# Schematic.net
KiCad netlist of a schematic drawn in EAGLE
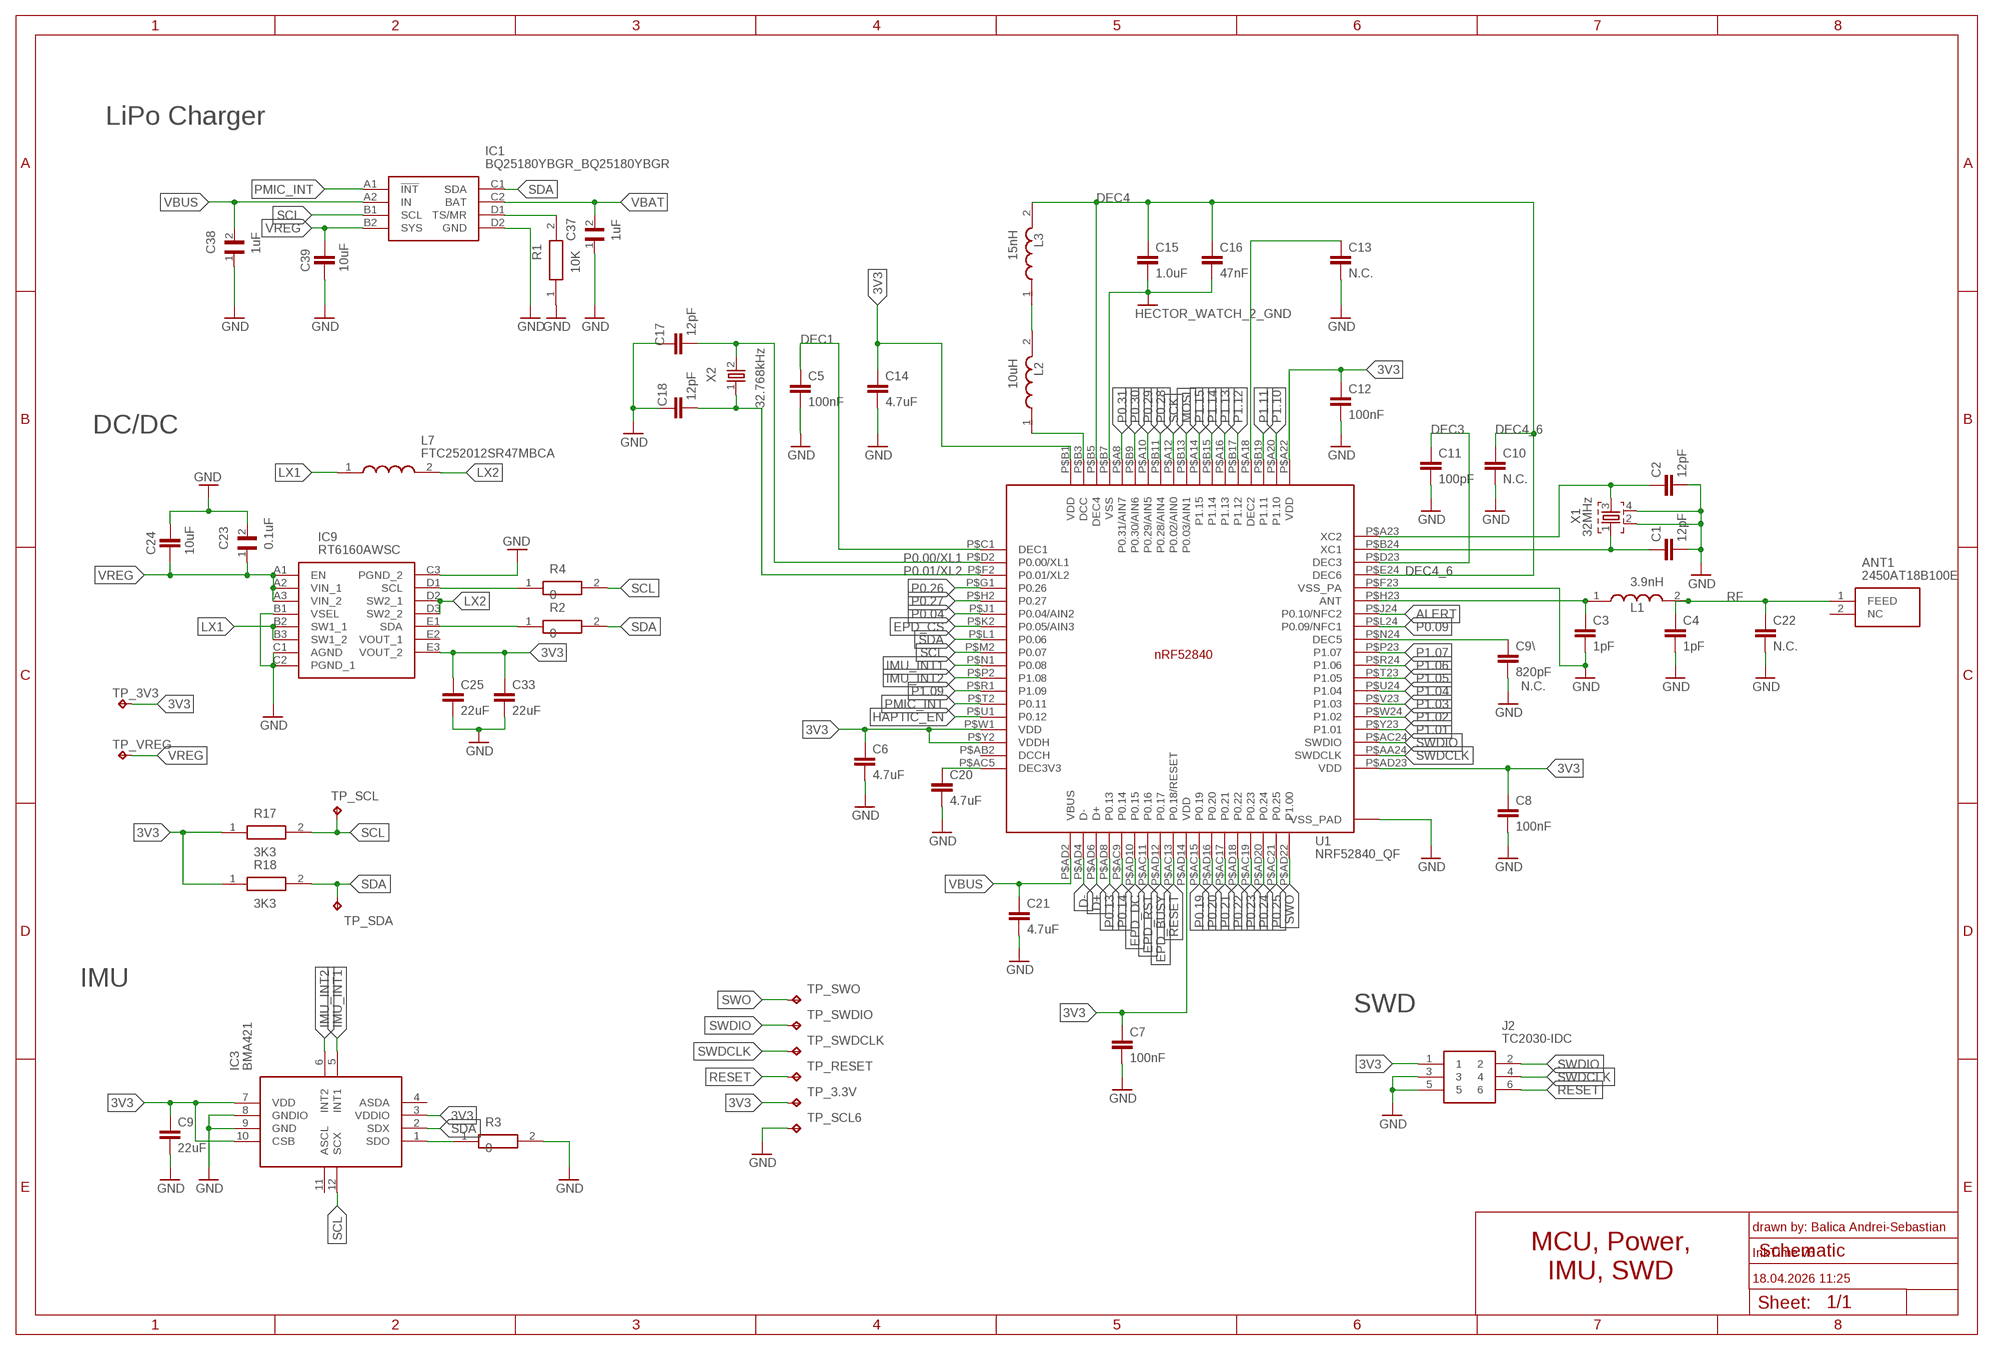
[diagram p0: schematic, sheet 1, part 1 of 2]
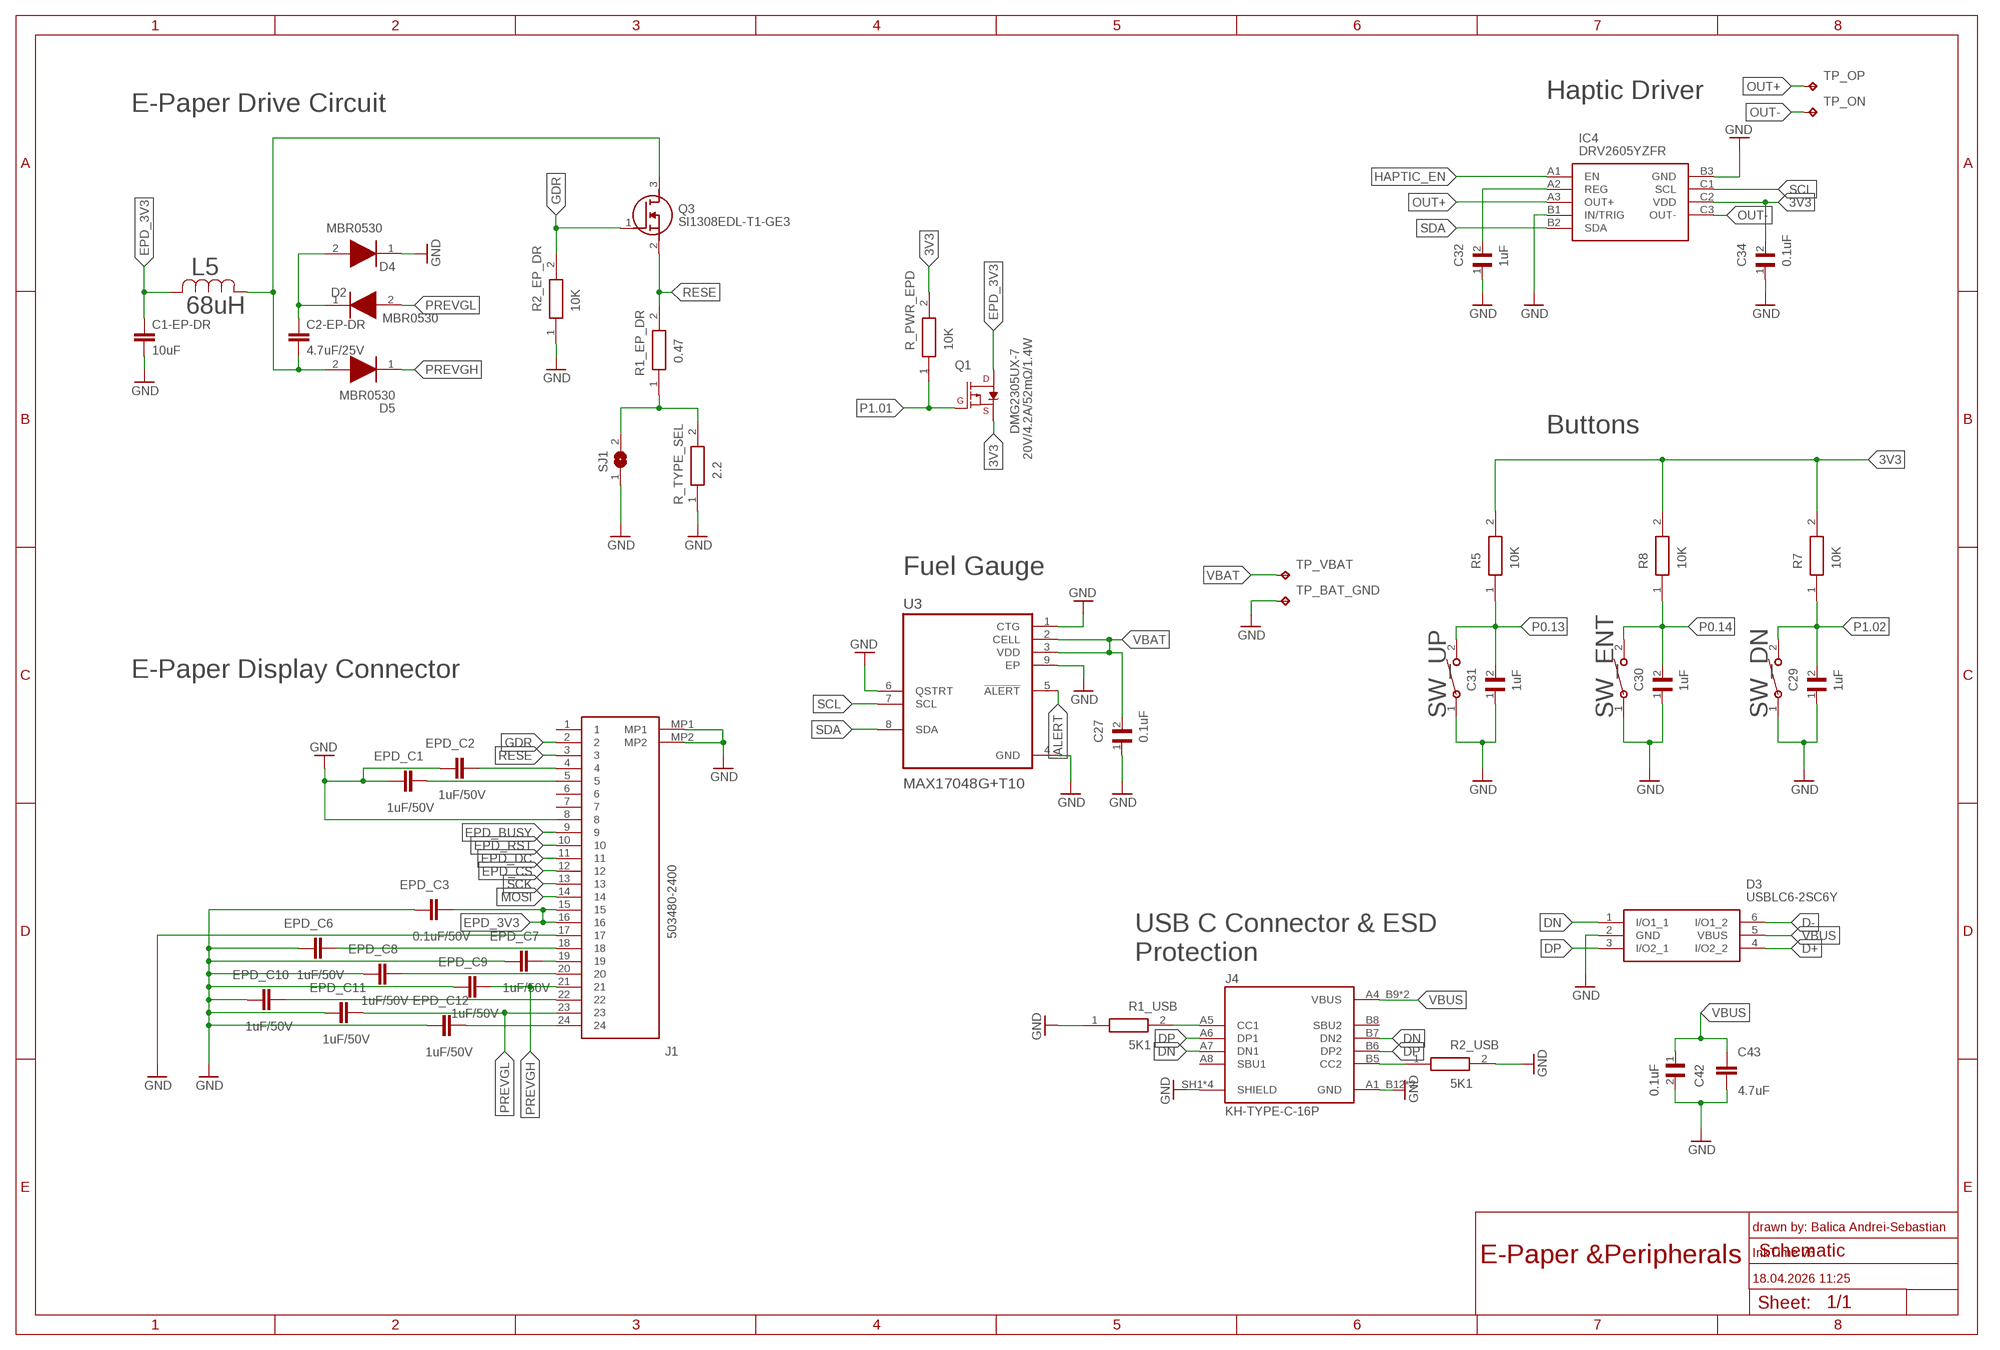
[diagram p1: schematic, sheet 1, part 2 of 2]

(export (version "E")
  (design (tool "Eeschema 10.0.6"))
  (components
    (comp (ref "ANT1")
      (value "2450AT18B100E")
      (footprint "eagle-import:2450AT18B100E_ANTC3216X140N")
      (fields (field (name "MOUSER_PART_NUMBER") "609-2450AT18B100E"))
      (libsource (lib "eagle-import") (part "2450AT18B100E_2450AT18B100E"))
    )
    (comp (ref "C1")
      (value "12pF")
      (footprint "eagle-import:NORDIC_NRF_3_RESC0201_L")
      (libsource (lib "eagle-import") (part "NORDIC_NRF_3_CAPACITOR_0201_L"))
    )
    (comp (ref "C1-EP-DR")
      (value "10uF")
      (footprint "eagle-import:NORDIC_NRF_3_RESC0201_L")
      (libsource (lib "eagle-import") (part "NORDIC_NRF_3_CAPACITOR_0201_L"))
    )
    (comp (ref "C2")
      (value "12pF")
      (footprint "eagle-import:NORDIC_NRF_3_RESC0201_L")
      (libsource (lib "eagle-import") (part "NORDIC_NRF_3_CAPACITOR_0201_L"))
    )
    (comp (ref "C2-EP-DR")
      (value "4.7uF/25V")
      (footprint "eagle-import:NORDIC_NRF_3_RESC0201_L")
      (libsource (lib "eagle-import") (part "NORDIC_NRF_3_CAPACITOR_0201_L"))
    )
    (comp (ref "C3")
      (value "1pF")
      (footprint "eagle-import:NORDIC_NRF_3_RESC0201_L")
      (libsource (lib "eagle-import") (part "NORDIC_NRF_3_CAPACITOR_0201_L"))
    )
    (comp (ref "C4")
      (value "1pF")
      (footprint "eagle-import:NORDIC_NRF_3_RESC0201_L")
      (libsource (lib "eagle-import") (part "NORDIC_NRF_3_CAPACITOR_0201_L"))
    )
    (comp (ref "C5")
      (value "100nF")
      (footprint "eagle-import:NORDIC_NRF_3_RESC0201_L")
      (libsource (lib "eagle-import") (part "NORDIC_NRF_3_CAPACITOR_0201_L"))
    )
    (comp (ref "C6")
      (value "4.7uF")
      (footprint "eagle-import:NORDIC_NRF_3_RESC0201_L")
      (libsource (lib "eagle-import") (part "NORDIC_NRF_3_CAPACITOR_0201_L"))
    )
    (comp (ref "C7")
      (value "100nF")
      (footprint "eagle-import:NORDIC_NRF_3_RESC0201_L")
      (libsource (lib "eagle-import") (part "NORDIC_NRF_3_CAPACITOR_0201_L"))
    )
    (comp (ref "C8")
      (value "100nF")
      (footprint "eagle-import:NORDIC_NRF_3_RESC0201_L")
      (libsource (lib "eagle-import") (part "NORDIC_NRF_3_CAPACITOR_0201_L"))
    )
    (comp (ref "C9")
      (value "22uF")
      (footprint "eagle-import:NORDIC_NRF_3_RESC0201_L")
      (libsource (lib "eagle-import") (part "NORDIC_NRF_3_CAPACITOR_0201_L"))
    )
    (comp (ref "C9\\")
      (value "820pF")
      (footprint "eagle-import:NORDIC_NRF_3_RESC0201_L")
      (libsource (lib "eagle-import") (part "NORDIC_NRF_3_CAPACITOR_0201_L"))
    )
    (comp (ref "C10")
      (value "N.C.")
      (footprint "eagle-import:NORDIC_NRF_3_RESC0201_L")
      (libsource (lib "eagle-import") (part "NORDIC_NRF_3_CAPACITOR_0201_L"))
    )
    (comp (ref "C11")
      (value "100pF")
      (footprint "eagle-import:NORDIC_NRF_3_RESC0201_L")
      (libsource (lib "eagle-import") (part "NORDIC_NRF_3_CAPACITOR_0201_L"))
    )
    (comp (ref "C12")
      (value "100nF")
      (footprint "eagle-import:NORDIC_NRF_3_RESC0201_L")
      (libsource (lib "eagle-import") (part "NORDIC_NRF_3_CAPACITOR_0201_L"))
    )
    (comp (ref "C13")
      (value "N.C.")
      (footprint "eagle-import:NORDIC_NRF_3_RESC0201_L")
      (libsource (lib "eagle-import") (part "NORDIC_NRF_3_CAPACITOR_0201_L"))
    )
    (comp (ref "C14")
      (value "4.7uF")
      (footprint "eagle-import:NORDIC_NRF_3_RESC0201_L")
      (libsource (lib "eagle-import") (part "NORDIC_NRF_3_CAPACITOR_0201_L"))
    )
    (comp (ref "C15")
      (value "1.0uF")
      (footprint "eagle-import:NORDIC_NRF_3_RESC0201_L")
      (libsource (lib "eagle-import") (part "NORDIC_NRF_3_CAPACITOR_0201_L"))
    )
    (comp (ref "C16")
      (value "47nF")
      (footprint "eagle-import:NORDIC_NRF_3_RESC0201_L")
      (libsource (lib "eagle-import") (part "NORDIC_NRF_3_CAPACITOR_0201_L"))
    )
    (comp (ref "C17")
      (value "12pF")
      (footprint "eagle-import:NORDIC_NRF_3_RESC0201_L")
      (libsource (lib "eagle-import") (part "NORDIC_NRF_3_CAPACITOR_0201_L"))
    )
    (comp (ref "C18")
      (value "12pF")
      (footprint "eagle-import:NORDIC_NRF_3_RESC0201_L")
      (libsource (lib "eagle-import") (part "NORDIC_NRF_3_CAPACITOR_0201_L"))
    )
    (comp (ref "C20")
      (value "4.7uF")
      (footprint "eagle-import:NORDIC_NRF_3_RESC0201_L")
      (libsource (lib "eagle-import") (part "NORDIC_NRF_3_CAPACITOR_0201_L"))
    )
    (comp (ref "C21")
      (value "4.7uF")
      (footprint "eagle-import:NORDIC_NRF_3_RESC0201_L")
      (libsource (lib "eagle-import") (part "NORDIC_NRF_3_CAPACITOR_0201_L"))
    )
    (comp (ref "C22")
      (value "N.C.")
      (footprint "eagle-import:NORDIC_NRF_3_RESC0201_L")
      (libsource (lib "eagle-import") (part "NORDIC_NRF_3_CAPACITOR_0201_L"))
    )
    (comp (ref "C23")
      (value "0.1uF")
      (footprint "eagle-import:GRM011R60J152KE01L_2_CAPC0201X13N")
      (fields (field (name "MF") "Murata") (field (name "MP") "GRM011R60J152KE01L"))
      (libsource (lib "eagle-import") (part "GRM011R60J152KE01L_2_GRM011R60J152KE01L"))
    )
    (comp (ref "C24")
      (value "10uF")
      (footprint "eagle-import:NORDIC_NRF_3_RESC0201_L")
      (libsource (lib "eagle-import") (part "NORDIC_NRF_3_CAPACITOR_0201_L"))
    )
    (comp (ref "C25")
      (value "22uF")
      (footprint "eagle-import:NORDIC_NRF_3_RESC0201_L")
      (libsource (lib "eagle-import") (part "NORDIC_NRF_3_CAPACITOR_0201_L"))
    )
    (comp (ref "C27")
      (value "0.1uF")
      (footprint "eagle-import:GRM011R60J152KE01L_2_CAPC0201X13N")
      (fields (field (name "MF") "Murata") (field (name "MP") "GRM011R60J152KE01L"))
      (libsource (lib "eagle-import") (part "GRM011R60J152KE01L_2_GRM011R60J152KE01L"))
    )
    (comp (ref "C29")
      (value "1uF")
      (footprint "eagle-import:GRM011R60J152KE01L_2_CAPC0201X13N")
      (fields (field (name "MF") "Murata") (field (name "MP") "GRM011R60J152KE01L"))
      (libsource (lib "eagle-import") (part "GRM011R60J152KE01L_2_GRM011R60J152KE01L"))
    )
    (comp (ref "C30")
      (value "1uF")
      (footprint "eagle-import:GRM011R60J152KE01L_2_CAPC0201X13N")
      (fields (field (name "MF") "Murata") (field (name "MP") "GRM011R60J152KE01L"))
      (libsource (lib "eagle-import") (part "GRM011R60J152KE01L_2_GRM011R60J152KE01L"))
    )
    (comp (ref "C31")
      (value "1uF")
      (footprint "eagle-import:GRM011R60J152KE01L_2_CAPC0201X13N")
      (fields (field (name "MF") "Murata") (field (name "MP") "GRM011R60J152KE01L"))
      (libsource (lib "eagle-import") (part "GRM011R60J152KE01L_2_GRM011R60J152KE01L"))
    )
    (comp (ref "C32")
      (value "1uF")
      (footprint "eagle-import:GRM011R60J152KE01L_2_CAPC0201X13N")
      (fields (field (name "MF") "Murata") (field (name "MP") "GRM011R60J152KE01L"))
      (libsource (lib "eagle-import") (part "GRM011R60J152KE01L_2_GRM011R60J152KE01L"))
    )
    (comp (ref "C33")
      (value "22uF")
      (footprint "eagle-import:NORDIC_NRF_3_RESC0201_L")
      (libsource (lib "eagle-import") (part "NORDIC_NRF_3_CAPACITOR_0201_L"))
    )
    (comp (ref "C34")
      (value "0.1uF")
      (footprint "eagle-import:GRM011R60J152KE01L_2_CAPC0201X13N")
      (fields (field (name "MF") "Murata") (field (name "MP") "GRM011R60J152KE01L"))
      (libsource (lib "eagle-import") (part "GRM011R60J152KE01L_2_GRM011R60J152KE01L"))
    )
    (comp (ref "C37")
      (value "1uF")
      (footprint "eagle-import:GRM011R60J152KE01L_2_CAPC0201X13N")
      (fields (field (name "MF") "Murata") (field (name "MP") "GRM011R60J152KE01L"))
      (libsource (lib "eagle-import") (part "GRM011R60J152KE01L_2_GRM011R60J152KE01L"))
    )
    (comp (ref "C38")
      (value "1uF")
      (footprint "eagle-import:GRM011R60J152KE01L_2_CAPC0201X13N")
      (fields (field (name "MF") "Murata") (field (name "MP") "GRM011R60J152KE01L"))
      (libsource (lib "eagle-import") (part "GRM011R60J152KE01L_2_GRM011R60J152KE01L"))
    )
    (comp (ref "C39")
      (value "10uF")
      (footprint "eagle-import:NORDIC_NRF_3_RESC0201_L")
      (libsource (lib "eagle-import") (part "NORDIC_NRF_3_CAPACITOR_0201_L"))
    )
    (comp (ref "C42")
      (value "0.1uF")
      (footprint "eagle-import:GRM011R60J152KE01L_2_CAPC0201X13N")
      (fields (field (name "MF") "Murata") (field (name "MP") "GRM011R60J152KE01L"))
      (libsource (lib "eagle-import") (part "GRM011R60J152KE01L_2_GRM011R60J152KE01L"))
    )
    (comp (ref "C43")
      (value "4.7uF")
      (footprint "eagle-import:NORDIC_NRF_3_RESC0201_L")
      (libsource (lib "eagle-import") (part "NORDIC_NRF_3_CAPACITOR_0201_L"))
    )
    (comp (ref "D2")
      (value "MBR0530")
      (footprint "eagle-import:ESP32_C6_LIBRARY_5_SOD3716X135N")
      (fields (field (name "MF") "ON Semiconductor"))
      (libsource (lib "eagle-import") (part "ESP32_C6_LIBRARY_5_MBR0530"))
    )
    (comp (ref "D3")
      (value "USBLC6-2SC6Y")
      (footprint "eagle-import:ESP32_C6_LIBRARY_3_SOT95P280X145-6N")
      (fields (field (name "MF") "STMicroelectronics"))
      (libsource (lib "eagle-import") (part "ESP32_C6_LIBRARY_3_USBLC6-2SC6Y"))
    )
    (comp (ref "D4")
      (value "MBR0530")
      (footprint "eagle-import:ESP32_C6_LIBRARY_5_SOD3716X135N")
      (fields (field (name "MF") "ON Semiconductor"))
      (libsource (lib "eagle-import") (part "ESP32_C6_LIBRARY_5_MBR0530"))
    )
    (comp (ref "D5")
      (value "MBR0530")
      (footprint "eagle-import:ESP32_C6_LIBRARY_5_SOD3716X135N")
      (fields (field (name "MF") "ON Semiconductor"))
      (libsource (lib "eagle-import") (part "ESP32_C6_LIBRARY_5_MBR0530"))
    )
    (comp (ref "EPD_C1")
      (value "1uF/50V")
      (footprint "eagle-import:NORDIC_NRF_3_RESC0201_L")
      (libsource (lib "eagle-import") (part "NORDIC_NRF_3_CAPACITOR_0201_L"))
    )
    (comp (ref "EPD_C2")
      (value "1uF/50V")
      (footprint "eagle-import:NORDIC_NRF_3_RESC0201_L")
      (libsource (lib "eagle-import") (part "NORDIC_NRF_3_CAPACITOR_0201_L"))
    )
    (comp (ref "EPD_C3")
      (value "0.1uF/50V")
      (footprint "eagle-import:NORDIC_NRF_3_RESC0201_L")
      (libsource (lib "eagle-import") (part "NORDIC_NRF_3_CAPACITOR_0201_L"))
    )
    (comp (ref "EPD_C6")
      (value "1uF/50V")
      (footprint "eagle-import:NORDIC_NRF_3_RESC0201_L")
      (libsource (lib "eagle-import") (part "NORDIC_NRF_3_CAPACITOR_0201_L"))
    )
    (comp (ref "EPD_C7")
      (value "1uF/50V")
      (footprint "eagle-import:NORDIC_NRF_3_RESC0201_L")
      (libsource (lib "eagle-import") (part "NORDIC_NRF_3_CAPACITOR_0201_L"))
    )
    (comp (ref "EPD_C8")
      (value "1uF/50V")
      (footprint "eagle-import:NORDIC_NRF_3_RESC0201_L")
      (libsource (lib "eagle-import") (part "NORDIC_NRF_3_CAPACITOR_0201_L"))
    )
    (comp (ref "EPD_C9")
      (value "1uF/50V")
      (footprint "eagle-import:NORDIC_NRF_3_RESC0201_L")
      (libsource (lib "eagle-import") (part "NORDIC_NRF_3_CAPACITOR_0201_L"))
    )
    (comp (ref "EPD_C10")
      (value "1uF/50V")
      (footprint "eagle-import:NORDIC_NRF_3_RESC0201_L")
      (libsource (lib "eagle-import") (part "NORDIC_NRF_3_CAPACITOR_0201_L"))
    )
    (comp (ref "EPD_C11")
      (value "1uF/50V")
      (footprint "eagle-import:NORDIC_NRF_3_RESC0201_L")
      (libsource (lib "eagle-import") (part "NORDIC_NRF_3_CAPACITOR_0201_L"))
    )
    (comp (ref "EPD_C12")
      (value "1uF/50V")
      (footprint "eagle-import:NORDIC_NRF_3_RESC0201_L")
      (libsource (lib "eagle-import") (part "NORDIC_NRF_3_CAPACITOR_0201_L"))
    )
    (comp (ref "IC1")
      (value "BQ25180YBGR_BQ25180YBGR")
      (footprint "eagle-import:BQ25180YBGR_BGA8C40P2X4_100X155X50")
      (fields
        (field (name "ARROW_PART_NUMBER") "BQ25180YBGR")
        (field (name "MOUSER_PART_NUMBER") "595-BQ25180YBGR")
      )
      (libsource (lib "eagle-import") (part "BQ25180YBGR_BQ25180YBGR"))
    )
    (comp (ref "IC3")
      (value "BMA421")
      (footprint "eagle-import:BMA423_BMA423")
      (fields (field (name "ARROW_PART_NUMBER") "BMA423") (field (name "MOUSER_PART_NUMBER") "262-BMA423"))
      (libsource (lib "eagle-import") (part "BMA423_BMA423"))
    )
    (comp (ref "IC4")
      (value "DRV2605YZFR")
      (footprint "eagle-import:DRV2605YZFR_BGA9C50P3X3_144X144X62")
      (libsource (lib "eagle-import") (part "DRV2605YZFR_DRV2605YZFR"))
    )
    (comp (ref "IC9")
      (value "RT6160AWSC")
      (footprint "eagle-import:RT6160AWSC_BGA15C40P3X5_140X230X60")
      (fields (field (name "MOUSER_PART_NUMBER") "835-RT6160AWSC"))
      (libsource (lib "eagle-import") (part "RT6160AWSC_RT6160AWSC"))
    )
    (comp (ref "J1")
      (value "503480-2400")
      (footprint "eagle-import:503480-2400_5034802400")
      (fields (field (name "MOUSER_PART_NUMBER") "538-503480-2400"))
      (libsource (lib "eagle-import") (part "503480-2400_503480-2400"))
    )
    (comp (ref "J2")
      (value "TC2030-IDC")
      (footprint "eagle-import:TC2030-IDC_TC2030IDC")
      (libsource (lib "eagle-import") (part "TC2030-IDC_TC2030-IDC"))
    )
    (comp (ref "J4")
      (value "KH-TYPE-C-16P")
      (footprint "eagle-import:KH-TYPE-C-16P_KINGHELM_KH-TYPE-C-16P")
      (fields (field (name "MF") "kinghelm"))
      (libsource (lib "eagle-import") (part "KH-TYPE-C-16P_KH-TYPE-C-16P"))
    )
    (comp (ref "L1")
      (value "3.9nH")
      (footprint "eagle-import:MLP2016SR47MT0S1_INDC2016X100N")
      (fields (field (name "MANUFACTURER_PART_NUMBER") "FTC252012SR47MBCA"))
      (libsource (lib "eagle-import") (part "MLP2016SR47MT0S1_FTC252012SR47MBCA"))
    )
    (comp (ref "L2")
      (value "10uH")
      (footprint "eagle-import:MLP2016SR47MT0S1_INDC2016X100N")
      (fields (field (name "MANUFACTURER_PART_NUMBER") "FTC252012SR47MBCA"))
      (libsource (lib "eagle-import") (part "MLP2016SR47MT0S1_FTC252012SR47MBCA"))
    )
    (comp (ref "L3")
      (value "15nH")
      (footprint "eagle-import:MLP2016SR47MT0S1_INDC2016X100N")
      (fields (field (name "MANUFACTURER_PART_NUMBER") "FTC252012SR47MBCA"))
      (libsource (lib "eagle-import") (part "MLP2016SR47MT0S1_FTC252012SR47MBCA"))
    )
    (comp (ref "L5")
      (value "68uH")
      (footprint "eagle-import:ESP32_C6_LIBRARY_2_IND_4828-WE-TPC_WRE")
      (fields
        (field (name "MANUFACTURER_PART_NUMBER") "744043680")
        (field (name "COPYRIGHT") "Copyright (C) 2024 Ultra Librarian. All rights reserved.")
      )
      (libsource (lib "eagle-import") (part "ESP32_C6_LIBRARY_2_744043680IND_4828-WE-TPC_WRE"))
    )
    (comp (ref "L7")
      (value "FTC252012SR47MBCA")
      (footprint "eagle-import:MLP2016SR47MT0S1_INDC2016X100N")
      (libsource (lib "eagle-import") (part "MLP2016SR47MT0S1_FTC252012SR47MBCA"))
    )
    (comp (ref "Q1")
      (value "20V/4.2A/52mΩ/1.4W")
      (footprint "eagle-import:ESP32_C6_LIBRARY_4_ESP32_C6_LIBRARY_4_ESP32_C6_LIBRARY_4_ESP32_C6_LIBRARY_4_ESP32_WROVER_SPARKFUN-DISCRETESEMI_SOT23-3")
      (libsource (lib "eagle-import") (part "ESP32_C6_LIBRARY_4_ESP32_WROVER_SPARKFUN-DISCRETESEMI_MOSFET_PCH-DMG2305UX-7"))
    )
    (comp (ref "Q3")
      (value "SI1308EDL-T1-GE3")
      (footprint "eagle-import:ESP32_C6_LIBRARY_6_SOT65P210X110-3N")
      (fields (field (name "MF") "Vishay Siliconix"))
      (libsource (lib "eagle-import") (part "ESP32_C6_LIBRARY_6_SI1308EDL-T1-GE3"))
    )
    (comp (ref "R1")
      (value "10K")
      (footprint "eagle-import:ERA-1AEB3401C_0201")
      (libsource (lib "eagle-import") (part "ERA-1AEB3401C_CPF0201D7K68C1"))
    )
    (comp (ref "R1_EP_DR")
      (value "0.47")
      (footprint "eagle-import:ERA-1AEB3401C_0201")
      (libsource (lib "eagle-import") (part "ERA-1AEB3401C_CPF0201D7K68C1"))
    )
    (comp (ref "R1_USB")
      (value "5K1")
      (footprint "eagle-import:ERA-1AEB3401C_0201")
      (libsource (lib "eagle-import") (part "ERA-1AEB3401C_CPF0201D7K68C1"))
    )
    (comp (ref "R2")
      (value "0")
      (footprint "eagle-import:ERA-1AEB3401C_0201")
      (libsource (lib "eagle-import") (part "ERA-1AEB3401C_CPF0201D7K68C1"))
    )
    (comp (ref "R2_EP_DR")
      (value "10K")
      (footprint "eagle-import:ERA-1AEB3401C_0201")
      (libsource (lib "eagle-import") (part "ERA-1AEB3401C_CPF0201D7K68C1"))
    )
    (comp (ref "R2_USB")
      (value "5K1")
      (footprint "eagle-import:ERA-1AEB3401C_0201")
      (libsource (lib "eagle-import") (part "ERA-1AEB3401C_CPF0201D7K68C1"))
    )
    (comp (ref "R3")
      (value "0")
      (footprint "eagle-import:ERA-1AEB3401C_0201")
      (libsource (lib "eagle-import") (part "ERA-1AEB3401C_CPF0201D7K68C1"))
    )
    (comp (ref "R4")
      (value "0")
      (footprint "eagle-import:ERA-1AEB3401C_0201")
      (libsource (lib "eagle-import") (part "ERA-1AEB3401C_CPF0201D7K68C1"))
    )
    (comp (ref "R5")
      (value "10K")
      (footprint "eagle-import:ERA-1AEB3401C_0201")
      (libsource (lib "eagle-import") (part "ERA-1AEB3401C_CPF0201D7K68C1"))
    )
    (comp (ref "R7")
      (value "10K")
      (footprint "eagle-import:ERA-1AEB3401C_0201")
      (libsource (lib "eagle-import") (part "ERA-1AEB3401C_CPF0201D7K68C1"))
    )
    (comp (ref "R8")
      (value "10K")
      (footprint "eagle-import:ERA-1AEB3401C_0201")
      (libsource (lib "eagle-import") (part "ERA-1AEB3401C_CPF0201D7K68C1"))
    )
    (comp (ref "R17")
      (value "3K3")
      (footprint "eagle-import:ERA-1AEB3401C_0201")
      (libsource (lib "eagle-import") (part "ERA-1AEB3401C_CPF0201D7K68C1"))
    )
    (comp (ref "R18")
      (value "3K3")
      (footprint "eagle-import:ERA-1AEB3401C_0201")
      (libsource (lib "eagle-import") (part "ERA-1AEB3401C_CPF0201D7K68C1"))
    )
    (comp (ref "R_PWR_EPD")
      (value "10K")
      (footprint "eagle-import:ERA-1AEB3401C_0201")
      (libsource (lib "eagle-import") (part "ERA-1AEB3401C_CPF0201D7K68C1"))
    )
    (comp (ref "R_TYPE_SEL")
      (value "2.2")
      (footprint "eagle-import:ERA-1AEB3401C_0201")
      (libsource (lib "eagle-import") (part "ERA-1AEB3401C_CPF0201D7K68C1"))
    )
    (comp (ref "SJ1")
      (value "ESP32_C6_LIBRARY_7_JUMPER_SJ")
      (footprint "eagle-import:ESP32_C6_LIBRARY_7_JUMPER_SJ")
      (libsource (lib "eagle-import") (part "ESP32_C6_LIBRARY_7_JUMPER_SJ"))
    )
    (comp (ref "SW_DN")
      (value "2025-10-22_07-23-44_LIBRARY_EVP-AKE31ASW_EVP-AKE31A_PAN")
      (footprint "eagle-import:2025-10-22_07-23-44_LIBRARY_SW_EVP-AKE31A_PAN")
      (fields
        (field (name "MANUFACTURER_PART_NUMBER") "EVP-AKE31A")
        (field (name "COPYRIGHT") "Copyright (C) 2025 Ultra Librarian. All rights reserved.")
      )
      (libsource (lib "eagle-import") (part "2025-10-22_07-23-44_LIBRARY_EVP-AKE31ASW_EVP-AKE31A_PAN"))
    )
    (comp (ref "SW_ENT")
      (value "2025-10-22_07-23-44_LIBRARY_EVP-AKE31ASW_EVP-AKE31A_PAN")
      (footprint "eagle-import:2025-10-22_07-23-44_LIBRARY_SW_EVP-AKE31A_PAN")
      (fields
        (field (name "MANUFACTURER_PART_NUMBER") "EVP-AKE31A")
        (field (name "COPYRIGHT") "Copyright (C) 2025 Ultra Librarian. All rights reserved.")
      )
      (libsource (lib "eagle-import") (part "2025-10-22_07-23-44_LIBRARY_EVP-AKE31ASW_EVP-AKE31A_PAN"))
    )
    (comp (ref "SW_UP")
      (value "2025-10-22_07-23-44_LIBRARY_EVP-AKE31ASW_EVP-AKE31A_PAN")
      (footprint "eagle-import:2025-10-22_07-23-44_LIBRARY_SW_EVP-AKE31A_PAN")
      (fields
        (field (name "MANUFACTURER_PART_NUMBER") "EVP-AKE31A")
        (field (name "COPYRIGHT") "Copyright (C) 2025 Ultra Librarian. All rights reserved.")
      )
      (libsource (lib "eagle-import") (part "2025-10-22_07-23-44_LIBRARY_EVP-AKE31ASW_EVP-AKE31A_PAN"))
    )
    (comp (ref "TP_3.3V")
      (value "HECTOR_WATCH_1_TPTP20R")
      (footprint "eagle-import:HECTOR_WATCH_1_TP20R")
      (libsource (lib "eagle-import") (part "HECTOR_WATCH_1_TPTP20R"))
    )
    (comp (ref "TP_3V3")
      (value "HECTOR_WATCH_1_TPTP20R")
      (footprint "eagle-import:HECTOR_WATCH_1_TP20R")
      (libsource (lib "eagle-import") (part "HECTOR_WATCH_1_TPTP20R"))
    )
    (comp (ref "TP_BAT_GND")
      (value "HECTOR_WATCH_1_TPTP20R")
      (footprint "eagle-import:HECTOR_WATCH_1_TP20R")
      (libsource (lib "eagle-import") (part "HECTOR_WATCH_1_TPTP20R"))
    )
    (comp (ref "TP_ON")
      (value "HECTOR_WATCH_1_TPTP20R")
      (footprint "eagle-import:HECTOR_WATCH_1_TP20R")
      (libsource (lib "eagle-import") (part "HECTOR_WATCH_1_TPTP20R"))
    )
    (comp (ref "TP_OP")
      (value "HECTOR_WATCH_1_TPTP20R")
      (footprint "eagle-import:HECTOR_WATCH_1_TP20R")
      (libsource (lib "eagle-import") (part "HECTOR_WATCH_1_TPTP20R"))
    )
    (comp (ref "TP_RESET")
      (value "HECTOR_WATCH_1_TPTP20R")
      (footprint "eagle-import:HECTOR_WATCH_1_TP20R")
      (libsource (lib "eagle-import") (part "HECTOR_WATCH_1_TPTP20R"))
    )
    (comp (ref "TP_SCL")
      (value "HECTOR_WATCH_1_TPTP20R")
      (footprint "eagle-import:HECTOR_WATCH_1_TP20R")
      (libsource (lib "eagle-import") (part "HECTOR_WATCH_1_TPTP20R"))
    )
    (comp (ref "TP_SCL6")
      (value "HECTOR_WATCH_1_TPTP20R")
      (footprint "eagle-import:HECTOR_WATCH_1_TP20R")
      (libsource (lib "eagle-import") (part "HECTOR_WATCH_1_TPTP20R"))
    )
    (comp (ref "TP_SDA")
      (value "HECTOR_WATCH_1_TPTP20R")
      (footprint "eagle-import:HECTOR_WATCH_1_TP20R")
      (libsource (lib "eagle-import") (part "HECTOR_WATCH_1_TPTP20R"))
    )
    (comp (ref "TP_SWDCLK")
      (value "HECTOR_WATCH_1_TPTP20R")
      (footprint "eagle-import:HECTOR_WATCH_1_TP20R")
      (libsource (lib "eagle-import") (part "HECTOR_WATCH_1_TPTP20R"))
    )
    (comp (ref "TP_SWDIO")
      (value "HECTOR_WATCH_1_TPTP20R")
      (footprint "eagle-import:HECTOR_WATCH_1_TP20R")
      (libsource (lib "eagle-import") (part "HECTOR_WATCH_1_TPTP20R"))
    )
    (comp (ref "TP_SWO")
      (value "HECTOR_WATCH_1_TPTP20R")
      (footprint "eagle-import:HECTOR_WATCH_1_TP20R")
      (libsource (lib "eagle-import") (part "HECTOR_WATCH_1_TPTP20R"))
    )
    (comp (ref "TP_VBAT")
      (value "HECTOR_WATCH_1_TPTP20R")
      (footprint "eagle-import:HECTOR_WATCH_1_TP20R")
      (libsource (lib "eagle-import") (part "HECTOR_WATCH_1_TPTP20R"))
    )
    (comp (ref "TP_VREG")
      (value "HECTOR_WATCH_1_TPTP20R")
      (footprint "eagle-import:HECTOR_WATCH_1_TP20R")
      (libsource (lib "eagle-import") (part "HECTOR_WATCH_1_TPTP20R"))
    )
    (comp (ref "U1")
      (value "NRF52840_QF")
      (footprint "eagle-import:NORDIC_NRF_4_AQFN50P700X700X85_HS-74N")
      (libsource (lib "eagle-import") (part "NORDIC_NRF_4_NRF52840_QF"))
    )
    (comp (ref "U3")
      (value "MAX17048G+T10")
      (footprint "eagle-import:ESP32_C6_LIBRARY_SON50P200X200X80-9N")
      (fields (field (name "MF") "Analog Devices"))
      (libsource (lib "eagle-import") (part "ESP32_C6_LIBRARY_MAX17048G+T10"))
    )
    (comp (ref "X1")
      (value "32MHz")
      (footprint "eagle-import:NORDIC_NRF_BT-XTAL_2016_N")
      (libsource (lib "eagle-import") (part "NORDIC_NRF_XTAL_32MHZ"))
    )
    (comp (ref "X2")
      (value "32.768kHz")
      (footprint "eagle-import:NORDIC_NRF_1_XTAL_3215_N")
      (libsource (lib "eagle-import") (part "NORDIC_NRF_1_XTAL_32KHZ"))
    )
  )
  (nets
    (net (code "1") (name "/DEC3") (class "Default")
      (node (ref "C11") (pin "1") (pinfunction "1_1") (pintype "passive"))
      (node (ref "U1") (pin "P$D23") (pinfunction "DEC3_P$D23") (pintype "bidirectional"))
    )
    (net (code "2") (name "/DEC4_6") (class "Default")
      (node (ref "C10") (pin "1") (pinfunction "1_1") (pintype "passive"))
      (node (ref "C15") (pin "1") (pinfunction "1_1") (pintype "passive"))
      (node (ref "C16") (pin "1") (pinfunction "1_1") (pintype "passive"))
      (node (ref "L3") (pin "2") (pinfunction "2_2") (pintype "bidirectional"))
      (node (ref "U1") (pin "P$B5") (pinfunction "DEC4_P$B5") (pintype "power_in"))
      (node (ref "U1") (pin "P$E24") (pinfunction "DEC6_P$E24") (pintype "bidirectional"))
    )
    (net (code "3") (name "/P0.00{slash}XL1") (class "Default")
      (node (ref "C17") (pin "2") (pinfunction "2_2") (pintype "passive"))
      (node (ref "U1") (pin "P$D2") (pinfunction "P0.00/XL1_P$D2") (pintype "bidirectional"))
      (node (ref "X2") (pin "2") (pinfunction "2_2") (pintype "passive"))
    )
    (net (code "4") (name "/P0.01{slash}XL2") (class "Default")
      (node (ref "C18") (pin "1") (pinfunction "1_1") (pintype "passive"))
      (node (ref "U1") (pin "P$F2") (pinfunction "P0.01/XL2_P$F2") (pintype "bidirectional"))
      (node (ref "X2") (pin "1") (pinfunction "1_1") (pintype "passive"))
    )
    (net (code "5") (name "/RF") (class "Default")
      (node (ref "ANT1") (pin "1") (pinfunction "FEED_1") (pintype "input"))
      (node (ref "C22") (pin "1") (pinfunction "1_1") (pintype "passive"))
      (node (ref "C4") (pin "1") (pinfunction "1_1") (pintype "passive"))
      (node (ref "L1") (pin "2") (pinfunction "2_2") (pintype "bidirectional"))
    )
    (net (code "6") (name "3V3") (class "Default")
      (node (ref "C12") (pin "1") (pinfunction "1_1") (pintype "passive"))
      (node (ref "C14") (pin "1") (pinfunction "1_1") (pintype "passive"))
      (node (ref "C25") (pin "1") (pinfunction "1_1") (pintype "passive"))
      (node (ref "C33") (pin "1") (pinfunction "1_1") (pintype "passive"))
      (node (ref "C34") (pin "2") (pinfunction "2_2") (pintype "passive"))
      (node (ref "C6") (pin "1") (pinfunction "1_1") (pintype "passive"))
      (node (ref "C7") (pin "1") (pinfunction "1_1") (pintype "passive"))
      (node (ref "C8") (pin "1") (pinfunction "1_1") (pintype "passive"))
      (node (ref "C9") (pin "1") (pinfunction "1_1") (pintype "passive"))
      (node (ref "IC3") (pin "10") (pinfunction "CSB_10") (pintype "bidirectional"))
      (node (ref "IC3") (pin "3") (pinfunction "VDDIO_3") (pintype "bidirectional"))
      (node (ref "IC3") (pin "7") (pinfunction "VDD_7") (pintype "bidirectional"))
      (node (ref "IC4") (pin "C2") (pinfunction "VDD_C2") (pintype "bidirectional"))
      (node (ref "IC9") (pin "E3") (pinfunction "VOUT_2_E3") (pintype "bidirectional"))
      (node (ref "J2") (pin "1") (pinfunction "1_1") (pintype "bidirectional"))
      (node (ref "Q1") (pin "2") (pinfunction "S_2") (pintype "bidirectional"))
      (node (ref "R17") (pin "1") (pinfunction "1_1") (pintype "bidirectional"))
      (node (ref "R18") (pin "1") (pinfunction "1_1") (pintype "bidirectional"))
      (node (ref "R5") (pin "2") (pinfunction "2_2") (pintype "bidirectional"))
      (node (ref "R7") (pin "2") (pinfunction "2_2") (pintype "bidirectional"))
      (node (ref "R8") (pin "2") (pinfunction "2_2") (pintype "bidirectional"))
      (node (ref "R_PWR_EPD") (pin "2") (pinfunction "2_2") (pintype "bidirectional"))
      (node (ref "TP_3.3V") (pin "TP") (pinfunction "TP_TP") (pintype "input"))
      (node (ref "TP_3V3") (pin "TP") (pinfunction "TP_TP") (pintype "input"))
      (node (ref "U1") (pin "P$A22") (pinfunction "VDD_P$A22") (pintype "power_in"))
      (node (ref "U1") (pin "P$AD14") (pinfunction "VDD_P$AD14") (pintype "power_in"))
      (node (ref "U1") (pin "P$AD23") (pinfunction "VDD_P$AD23") (pintype "power_in"))
      (node (ref "U1") (pin "P$B1") (pinfunction "VDD_P$B1") (pintype "power_in"))
      (node (ref "U1") (pin "P$W1") (pinfunction "VDD_P$W1") (pintype "power_in"))
      (node (ref "U1") (pin "P$Y2") (pinfunction "VDDH_P$Y2") (pintype "power_in"))
    )
    (net (code "7") (name "ALERT") (class "Default")
      (node (ref "U1") (pin "P$J24") (pinfunction "P0.10/NFC2_P$J24") (pintype "bidirectional"))
      (node (ref "U3") (pin "5") (pinfunction "~{ALERT}_5") (pintype "output"))
    )
    (net (code "8") (name "D+") (class "Default")
      (node (ref "D3") (pin "4") (pinfunction "I/O2_2_4") (pintype "bidirectional"))
      (node (ref "U1") (pin "P$AD6") (pinfunction "D+_P$AD6") (pintype "bidirectional"))
    )
    (net (code "9") (name "D-") (class "Default")
      (node (ref "D3") (pin "6") (pinfunction "I/O1_2_6") (pintype "bidirectional"))
      (node (ref "U1") (pin "P$AD4") (pinfunction "D-_P$AD4") (pintype "bidirectional"))
    )
    (net (code "10") (name "DN") (class "Default")
      (node (ref "D3") (pin "1") (pinfunction "I/O1_1_1") (pintype "bidirectional"))
      (node (ref "J4") (pin "A7") (pinfunction "DN1_A7") (pintype "bidirectional"))
      (node (ref "J4") (pin "B7") (pinfunction "DN2_B7") (pintype "bidirectional"))
    )
    (net (code "11") (name "DP") (class "Default")
      (node (ref "D3") (pin "3") (pinfunction "I/O2_1_3") (pintype "bidirectional"))
      (node (ref "J4") (pin "A6") (pinfunction "DP1_A6") (pintype "bidirectional"))
      (node (ref "J4") (pin "B6") (pinfunction "DP2_B6") (pintype "bidirectional"))
    )
    (net (code "12") (name "EPD_3V3") (class "Default")
      (node (ref "C1-EP-DR") (pin "1") (pinfunction "1_1") (pintype "passive"))
      (node (ref "EPD_C3") (pin "2") (pinfunction "2_2") (pintype "passive"))
      (node (ref "J1") (pin "15") (pinfunction "15_15") (pintype "bidirectional"))
      (node (ref "J1") (pin "16") (pinfunction "16_16") (pintype "bidirectional"))
      (node (ref "L5") (pin "2") (pinfunction "2_2") (pintype "passive"))
      (node (ref "Q1") (pin "3") (pinfunction "D_3") (pintype "bidirectional"))
    )
    (net (code "13") (name "EPD_BUSY") (class "Default")
      (node (ref "J1") (pin "9") (pinfunction "9_9") (pintype "bidirectional"))
      (node (ref "U1") (pin "P$AD12") (pinfunction "P0.17_P$AD12") (pintype "bidirectional"))
    )
    (net (code "14") (name "EPD_CS") (class "Default")
      (node (ref "J1") (pin "12") (pinfunction "12_12") (pintype "bidirectional"))
      (node (ref "U1") (pin "P$K2") (pinfunction "P0.05/AIN3_P$K2") (pintype "bidirectional"))
    )
    (net (code "15") (name "EPD_DC") (class "Default")
      (node (ref "J1") (pin "11") (pinfunction "11_11") (pintype "bidirectional"))
      (node (ref "U1") (pin "P$AD10") (pinfunction "P0.15_P$AD10") (pintype "bidirectional"))
    )
    (net (code "16") (name "EPD_RST") (class "Default")
      (node (ref "J1") (pin "10") (pinfunction "10_10") (pintype "bidirectional"))
      (node (ref "U1") (pin "P$AC11") (pinfunction "P0.16_P$AC11") (pintype "bidirectional"))
    )
    (net (code "17") (name "GDR") (class "Default")
      (node (ref "J1") (pin "2") (pinfunction "2_2") (pintype "bidirectional"))
      (node (ref "Q3") (pin "1") (pinfunction "G_1") (pintype "bidirectional"))
      (node (ref "R2_EP_DR") (pin "2") (pinfunction "2_2") (pintype "bidirectional"))
    )
    (net (code "18") (name "GND") (class "Default")
      (node (ref "C1") (pin "2") (pinfunction "2_2") (pintype "passive"))
      (node (ref "C1-EP-DR") (pin "2") (pinfunction "2_2") (pintype "passive"))
      (node (ref "C10") (pin "2") (pinfunction "2_2") (pintype "passive"))
      (node (ref "C11") (pin "2") (pinfunction "2_2") (pintype "passive"))
      (node (ref "C12") (pin "2") (pinfunction "2_2") (pintype "passive"))
      (node (ref "C13") (pin "2") (pinfunction "2_2") (pintype "passive"))
      (node (ref "C14") (pin "2") (pinfunction "2_2") (pintype "passive"))
      (node (ref "C15") (pin "2") (pinfunction "2_2") (pintype "passive"))
      (node (ref "C16") (pin "2") (pinfunction "2_2") (pintype "passive"))
      (node (ref "C17") (pin "1") (pinfunction "1_1") (pintype "passive"))
      (node (ref "C18") (pin "2") (pinfunction "2_2") (pintype "passive"))
      (node (ref "C2") (pin "2") (pinfunction "2_2") (pintype "passive"))
      (node (ref "C20") (pin "2") (pinfunction "2_2") (pintype "passive"))
      (node (ref "C21") (pin "2") (pinfunction "2_2") (pintype "passive"))
      (node (ref "C22") (pin "2") (pinfunction "2_2") (pintype "passive"))
      (node (ref "C23") (pin "2") (pinfunction "2_2") (pintype "passive"))
      (node (ref "C24") (pin "1") (pinfunction "1_1") (pintype "passive"))
      (node (ref "C25") (pin "2") (pinfunction "2_2") (pintype "passive"))
      (node (ref "C27") (pin "1") (pinfunction "1_1") (pintype "passive"))
      (node (ref "C29") (pin "1") (pinfunction "1_1") (pintype "passive"))
      (node (ref "C3") (pin "2") (pinfunction "2_2") (pintype "passive"))
      (node (ref "C30") (pin "1") (pinfunction "1_1") (pintype "passive"))
      (node (ref "C31") (pin "1") (pinfunction "1_1") (pintype "passive"))
      (node (ref "C32") (pin "1") (pinfunction "1_1") (pintype "passive"))
      (node (ref "C33") (pin "2") (pinfunction "2_2") (pintype "passive"))
      (node (ref "C34") (pin "1") (pinfunction "1_1") (pintype "passive"))
      (node (ref "C37") (pin "1") (pinfunction "1_1") (pintype "passive"))
      (node (ref "C38") (pin "1") (pinfunction "1_1") (pintype "passive"))
      (node (ref "C39") (pin "2") (pinfunction "2_2") (pintype "passive"))
      (node (ref "C4") (pin "2") (pinfunction "2_2") (pintype "passive"))
      (node (ref "C42") (pin "2") (pinfunction "2_2") (pintype "passive"))
      (node (ref "C43") (pin "2") (pinfunction "2_2") (pintype "passive"))
      (node (ref "C5") (pin "2") (pinfunction "2_2") (pintype "passive"))
      (node (ref "C6") (pin "2") (pinfunction "2_2") (pintype "passive"))
      (node (ref "C7") (pin "2") (pinfunction "2_2") (pintype "passive"))
      (node (ref "C8") (pin "2") (pinfunction "2_2") (pintype "passive"))
      (node (ref "C9") (pin "2") (pinfunction "2_2") (pintype "passive"))
      (node (ref "C9\\") (pin "2") (pinfunction "2_2") (pintype "passive"))
      (node (ref "D3") (pin "2") (pinfunction "GND_2") (pintype "bidirectional"))
      (node (ref "D4") (pin "1") (pinfunction "K_1") (pintype "bidirectional"))
      (node (ref "EPD_C1") (pin "1") (pinfunction "1_1") (pintype "passive"))
      (node (ref "EPD_C10") (pin "1") (pinfunction "1_1") (pintype "passive"))
      (node (ref "EPD_C11") (pin "1") (pinfunction "1_1") (pintype "passive"))
      (node (ref "EPD_C12") (pin "1") (pinfunction "1_1") (pintype "passive"))
      (node (ref "EPD_C2") (pin "1") (pinfunction "1_1") (pintype "passive"))
      (node (ref "EPD_C3") (pin "1") (pinfunction "1_1") (pintype "passive"))
      (node (ref "EPD_C6") (pin "1") (pinfunction "1_1") (pintype "passive"))
      (node (ref "EPD_C7") (pin "1") (pinfunction "1_1") (pintype "passive"))
      (node (ref "EPD_C8") (pin "1") (pinfunction "1_1") (pintype "passive"))
      (node (ref "EPD_C9") (pin "1") (pinfunction "1_1") (pintype "passive"))
      (node (ref "IC1") (pin "D2") (pinfunction "GND_D2") (pintype "bidirectional"))
      (node (ref "IC3") (pin "8") (pinfunction "GNDIO_8") (pintype "bidirectional"))
      (node (ref "IC3") (pin "9") (pinfunction "GND_9") (pintype "bidirectional"))
      (node (ref "IC4") (pin "B1") (pinfunction "IN/TRIG_B1") (pintype "bidirectional"))
      (node (ref "IC4") (pin "B3") (pinfunction "GND_B3") (pintype "bidirectional"))
      (node (ref "IC9") (pin "B1") (pinfunction "VSEL_B1") (pintype "bidirectional"))
      (node (ref "IC9") (pin "C1") (pinfunction "AGND_C1") (pintype "bidirectional"))
      (node (ref "IC9") (pin "C2") (pinfunction "PGND_1_C2") (pintype "bidirectional"))
      (node (ref "IC9") (pin "C3") (pinfunction "PGND_2_C3") (pintype "bidirectional"))
      (node (ref "J1") (pin "17") (pinfunction "17_17") (pintype "bidirectional"))
      (node (ref "J1") (pin "8") (pinfunction "8_8") (pintype "bidirectional"))
      (node (ref "J1") (pin "MP1") (pinfunction "MP1_MP1") (pintype "bidirectional"))
      (node (ref "J1") (pin "MP2") (pinfunction "MP2_MP2") (pintype "bidirectional"))
      (node (ref "J2") (pin "3") (pinfunction "3_3") (pintype "bidirectional"))
      (node (ref "J2") (pin "5") (pinfunction "5_5") (pintype "bidirectional"))
      (node (ref "J4") (pin "A12_B1") (pinfunction "GND_A12_B1") (pintype "power_in"))
      (node (ref "J4") (pin "A1_B12") (pinfunction "GND_A1_B12") (pintype "power_in"))
      (node (ref "J4") (pin "SH1") (pinfunction "SHIELD_SH1") (pintype "passive"))
      (node (ref "J4") (pin "SH2") (pinfunction "SHIELD_SH2") (pintype "passive"))
      (node (ref "J4") (pin "SH3") (pinfunction "SHIELD_SH3") (pintype "passive"))
      (node (ref "J4") (pin "SH4") (pinfunction "SHIELD_SH4") (pintype "passive"))
      (node (ref "R1") (pin "1") (pinfunction "1_1") (pintype "bidirectional"))
      (node (ref "R1_USB") (pin "1") (pinfunction "1_1") (pintype "bidirectional"))
      (node (ref "R2_EP_DR") (pin "1") (pinfunction "1_1") (pintype "bidirectional"))
      (node (ref "R2_USB") (pin "2") (pinfunction "2_2") (pintype "bidirectional"))
      (node (ref "R3") (pin "2") (pinfunction "2_2") (pintype "bidirectional"))
      (node (ref "R_TYPE_SEL") (pin "1") (pinfunction "1_1") (pintype "bidirectional"))
      (node (ref "SJ1") (pin "1") (pinfunction "1_1") (pintype "passive"))
      (node (ref "SW_DN") (pin "1") (pinfunction "1_1") (pintype "passive"))
      (node (ref "SW_ENT") (pin "1") (pinfunction "1_1") (pintype "passive"))
      (node (ref "SW_UP") (pin "1") (pinfunction "1_1") (pintype "passive"))
      (node (ref "TP_BAT_GND") (pin "TP") (pinfunction "TP_TP") (pintype "input"))
      (node (ref "TP_SCL6") (pin "TP") (pinfunction "TP_TP") (pintype "input"))
      (node (ref "U1") (pin "P$74") (pinfunction "VSS_PAD_P$74") (pintype "bidirectional"))
      (node (ref "U1") (pin "P$75") (pinfunction "VSS_PAD_P$75") (pintype "bidirectional"))
      (node (ref "U1") (pin "P$76") (pinfunction "VSS_PAD_P$76") (pintype "bidirectional"))
      (node (ref "U1") (pin "P$77") (pinfunction "VSS_PAD_P$77") (pintype "bidirectional"))
      (node (ref "U1") (pin "P$78") (pinfunction "VSS_PAD_P$78") (pintype "bidirectional"))
      (node (ref "U1") (pin "P$79") (pinfunction "VSS_PAD_P$79") (pintype "bidirectional"))
      (node (ref "U1") (pin "P$80") (pinfunction "VSS_PAD_P$80") (pintype "bidirectional"))
      (node (ref "U1") (pin "P$81") (pinfunction "VSS_PAD_P$81") (pintype "bidirectional"))
      (node (ref "U1") (pin "P$82") (pinfunction "VSS_PAD_P$82") (pintype "bidirectional"))
      (node (ref "U1") (pin "P$83") (pinfunction "VSS_PAD_P$83") (pintype "bidirectional"))
      (node (ref "U1") (pin "P$84") (pinfunction "VSS_PAD_P$84") (pintype "bidirectional"))
      (node (ref "U1") (pin "P$85") (pinfunction "VSS_PAD_P$85") (pintype "bidirectional"))
      (node (ref "U1") (pin "P$86") (pinfunction "VSS_PAD_P$86") (pintype "bidirectional"))
      (node (ref "U1") (pin "P$87") (pinfunction "VSS_PAD_P$87") (pintype "bidirectional"))
      (node (ref "U1") (pin "P$88") (pinfunction "VSS_PAD_P$88") (pintype "bidirectional"))
      (node (ref "U1") (pin "P$89") (pinfunction "VSS_PAD_P$89") (pintype "bidirectional"))
      (node (ref "U1") (pin "P$90") (pinfunction "VSS_PAD_P$90") (pintype "bidirectional"))
      (node (ref "U1") (pin "P$B7") (pinfunction "VSS_P$B7") (pintype "power_in"))
      (node (ref "U1") (pin "P$F23") (pinfunction "VSS_PA_P$F23") (pintype "bidirectional"))
      (node (ref "U3") (pin "1") (pinfunction "CTG_1") (pintype "power_in"))
      (node (ref "U3") (pin "4") (pinfunction "GND_4") (pintype "power_in"))
      (node (ref "U3") (pin "6") (pinfunction "QSTRT_6") (pintype "input"))
      (node (ref "U3") (pin "9") (pinfunction "EP_9") (pintype "power_in"))
      (node (ref "X1") (pin "2") (pinfunction "2_2") (pintype "passive"))
      (node (ref "X1") (pin "4") (pinfunction "4_4") (pintype "passive"))
    )
    (net (code "19") (name "HAPTIC_EN") (class "Default")
      (node (ref "IC4") (pin "A1") (pinfunction "EN_A1") (pintype "bidirectional"))
      (node (ref "U1") (pin "P$U1") (pinfunction "P0.12_P$U1") (pintype "bidirectional"))
    )
    (net (code "20") (name "IMU_INT1") (class "Default")
      (node (ref "IC3") (pin "5") (pinfunction "INT1_5") (pintype "bidirectional"))
      (node (ref "U1") (pin "P$N1") (pinfunction "P0.08_P$N1") (pintype "bidirectional"))
    )
    (net (code "21") (name "IMU_INT2") (class "Default")
      (node (ref "IC3") (pin "6") (pinfunction "INT2_6") (pintype "bidirectional"))
      (node (ref "U1") (pin "P$P2") (pinfunction "P1.08_P$P2") (pintype "bidirectional"))
    )
    (net (code "22") (name "LX1") (class "Default")
      (node (ref "IC9") (pin "B2") (pinfunction "SW1_1_B2") (pintype "bidirectional"))
      (node (ref "IC9") (pin "B3") (pinfunction "SW1_2_B3") (pintype "bidirectional"))
      (node (ref "L7") (pin "1") (pinfunction "1_1") (pintype "bidirectional"))
    )
    (net (code "23") (name "LX2") (class "Default")
      (node (ref "IC9") (pin "D2") (pinfunction "SW2_1_D2") (pintype "bidirectional"))
      (node (ref "IC9") (pin "D3") (pinfunction "SW2_2_D3") (pintype "bidirectional"))
      (node (ref "L7") (pin "2") (pinfunction "2_2") (pintype "bidirectional"))
    )
    (net (code "24") (name "MOSI") (class "Default")
      (node (ref "J1") (pin "14") (pinfunction "14_14") (pintype "bidirectional"))
      (node (ref "U1") (pin "P$B13") (pinfunction "P0.03/AIN1_P$B13") (pintype "bidirectional"))
    )
    (net (code "25") (name "Net-(D2-K)") (class "Default")
      (node (ref "C2-EP-DR") (pin "1") (pinfunction "1_1") (pintype "passive"))
      (node (ref "D2") (pin "1") (pinfunction "K_1") (pintype "bidirectional"))
      (node (ref "D4") (pin "2") (pinfunction "A_2") (pintype "bidirectional"))
    )
    (net (code "26") (name "Net-(D5-A)") (class "Default")
      (node (ref "C2-EP-DR") (pin "2") (pinfunction "2_2") (pintype "passive"))
      (node (ref "D5") (pin "2") (pinfunction "A_2") (pintype "bidirectional"))
      (node (ref "L5") (pin "1") (pinfunction "1_1") (pintype "passive"))
      (node (ref "Q3") (pin "3") (pinfunction "D_3") (pintype "bidirectional"))
    )
    (net (code "27") (name "Net-(EPD_C1-Pad2)") (class "Default")
      (node (ref "EPD_C1") (pin "2") (pinfunction "2_2") (pintype "passive"))
      (node (ref "J1") (pin "5") (pinfunction "5_5") (pintype "bidirectional"))
    )
    (net (code "28") (name "Net-(EPD_C2-Pad2)") (class "Default")
      (node (ref "EPD_C2") (pin "2") (pinfunction "2_2") (pintype "passive"))
      (node (ref "J1") (pin "4") (pinfunction "4_4") (pintype "bidirectional"))
    )
    (net (code "29") (name "Net-(EPD_C6-Pad2)") (class "Default")
      (node (ref "EPD_C6") (pin "2") (pinfunction "2_2") (pintype "passive"))
      (node (ref "J1") (pin "18") (pinfunction "18_18") (pintype "bidirectional"))
    )
    (net (code "30") (name "Net-(EPD_C7-Pad2)") (class "Default")
      (node (ref "EPD_C7") (pin "2") (pinfunction "2_2") (pintype "passive"))
      (node (ref "J1") (pin "19") (pinfunction "19_19") (pintype "bidirectional"))
    )
    (net (code "31") (name "Net-(EPD_C8-Pad2)") (class "Default")
      (node (ref "EPD_C8") (pin "2") (pinfunction "2_2") (pintype "passive"))
      (node (ref "J1") (pin "20") (pinfunction "20_20") (pintype "bidirectional"))
    )
    (net (code "32") (name "Net-(EPD_C10-Pad2)") (class "Default")
      (node (ref "EPD_C10") (pin "2") (pinfunction "2_2") (pintype "passive"))
      (node (ref "J1") (pin "22") (pinfunction "22_22") (pintype "bidirectional"))
    )
    (net (code "33") (name "Net-(EPD_C12-Pad2)") (class "Default")
      (node (ref "EPD_C12") (pin "2") (pinfunction "2_2") (pintype "passive"))
      (node (ref "J1") (pin "24") (pinfunction "24_24") (pintype "bidirectional"))
    )
    (net (code "34") (name "Net-(IC1-TS{slash}MR)") (class "Default")
      (node (ref "IC1") (pin "D1") (pinfunction "TS/MR_D1") (pintype "bidirectional"))
      (node (ref "R1") (pin "2") (pinfunction "2_2") (pintype "bidirectional"))
    )
    (net (code "35") (name "Net-(IC3-SDO)") (class "Default")
      (node (ref "IC3") (pin "1") (pinfunction "SDO_1") (pintype "bidirectional"))
      (node (ref "R3") (pin "1") (pinfunction "1_1") (pintype "bidirectional"))
    )
    (net (code "36") (name "Net-(IC4-REG)") (class "Default")
      (node (ref "C32") (pin "2") (pinfunction "2_2") (pintype "passive"))
      (node (ref "IC4") (pin "A2") (pinfunction "REG_A2") (pintype "bidirectional"))
    )
    (net (code "37") (name "Net-(IC9-SCL)") (class "Default")
      (node (ref "IC9") (pin "D1") (pinfunction "SCL_D1") (pintype "bidirectional"))
      (node (ref "R4") (pin "1") (pinfunction "1_1") (pintype "bidirectional"))
    )
    (net (code "38") (name "Net-(IC9-SDA)") (class "Default")
      (node (ref "IC9") (pin "E1") (pinfunction "SDA_E1") (pintype "bidirectional"))
      (node (ref "R2") (pin "1") (pinfunction "1_1") (pintype "bidirectional"))
    )
    (net (code "39") (name "Net-(J4-CC1)") (class "Default")
      (node (ref "J4") (pin "A5") (pinfunction "CC1_A5") (pintype "bidirectional"))
      (node (ref "R1_USB") (pin "2") (pinfunction "2_2") (pintype "bidirectional"))
    )
    (net (code "40") (name "Net-(J4-CC2)") (class "Default")
      (node (ref "J4") (pin "B5") (pinfunction "CC2_B5") (pintype "bidirectional"))
      (node (ref "R2_USB") (pin "1") (pinfunction "1_1") (pintype "bidirectional"))
    )
    (net (code "41") (name "Net-(L2-Pad2)") (class "Default")
      (node (ref "L2") (pin "2") (pinfunction "2_2") (pintype "bidirectional"))
      (node (ref "L3") (pin "1") (pinfunction "1_1") (pintype "bidirectional"))
    )
    (net (code "42") (name "Net-(R1_EP_DR-Pad1)") (class "Default")
      (node (ref "R1_EP_DR") (pin "1") (pinfunction "1_1") (pintype "bidirectional"))
      (node (ref "R_TYPE_SEL") (pin "2") (pinfunction "2_2") (pintype "bidirectional"))
      (node (ref "SJ1") (pin "2") (pinfunction "2_2") (pintype "passive"))
    )
    (net (code "43") (name "Net-(U1-ANT)") (class "Default")
      (node (ref "C3") (pin "1") (pinfunction "1_1") (pintype "passive"))
      (node (ref "L1") (pin "1") (pinfunction "1_1") (pintype "bidirectional"))
      (node (ref "U1") (pin "P$H23") (pinfunction "ANT_P$H23") (pintype "bidirectional"))
    )
    (net (code "44") (name "Net-(U1-DCC)") (class "Default")
      (node (ref "L2") (pin "1") (pinfunction "1_1") (pintype "bidirectional"))
      (node (ref "U1") (pin "P$B3") (pinfunction "DCC_P$B3") (pintype "output"))
    )
    (net (code "45") (name "Net-(U1-DEC1)") (class "Default")
      (node (ref "C5") (pin "1") (pinfunction "1_1") (pintype "passive"))
      (node (ref "U1") (pin "P$C1") (pinfunction "DEC1_P$C1") (pintype "power_in"))
    )
    (net (code "46") (name "Net-(U1-DEC2)") (class "Default")
      (node (ref "C13") (pin "1") (pinfunction "1_1") (pintype "passive"))
      (node (ref "U1") (pin "P$A18") (pinfunction "DEC2_P$A18") (pintype "bidirectional"))
    )
    (net (code "47") (name "Net-(U1-DEC3V3)") (class "Default")
      (node (ref "C20") (pin "1") (pinfunction "1_1") (pintype "passive"))
      (node (ref "U1") (pin "P$AC5") (pinfunction "DEC3V3_P$AC5") (pintype "bidirectional"))
    )
    (net (code "48") (name "Net-(U1-DEC5)") (class "Default")
      (node (ref "C9\\") (pin "1") (pinfunction "1_1") (pintype "passive"))
      (node (ref "U1") (pin "P$N24") (pinfunction "DEC5_P$N24") (pintype "bidirectional"))
    )
    (net (code "49") (name "Net-(U1-XC1)") (class "Default")
      (node (ref "C1") (pin "1") (pinfunction "1_1") (pintype "passive"))
      (node (ref "U1") (pin "P$B24") (pinfunction "XC1_P$B24") (pintype "input"))
      (node (ref "X1") (pin "1") (pinfunction "1_1") (pintype "passive"))
    )
    (net (code "50") (name "Net-(U1-XC2)") (class "Default")
      (node (ref "C2") (pin "1") (pinfunction "1_1") (pintype "passive"))
      (node (ref "U1") (pin "P$A23") (pinfunction "XC2_P$A23") (pintype "output"))
      (node (ref "X1") (pin "3") (pinfunction "3_3") (pintype "passive"))
    )
    (net (code "51") (name "OUT+") (class "Default")
      (node (ref "IC4") (pin "A3") (pinfunction "OUT+_A3") (pintype "bidirectional"))
      (node (ref "TP_OP") (pin "TP") (pinfunction "TP_TP") (pintype "input"))
    )
    (net (code "52") (name "OUT-") (class "Default")
      (node (ref "IC4") (pin "C3") (pinfunction "OUT-_C3") (pintype "bidirectional"))
      (node (ref "TP_ON") (pin "TP") (pinfunction "TP_TP") (pintype "input"))
    )
    (net (code "53") (name "P0.04") (class "Default")
      (node (ref "U1") (pin "P$J1") (pinfunction "P0.04/AIN2_P$J1") (pintype "bidirectional"))
    )
    (net (code "54") (name "P0.09") (class "Default")
      (node (ref "U1") (pin "P$L24") (pinfunction "P0.09/NFC1_P$L24") (pintype "bidirectional"))
    )
    (net (code "55") (name "P0.13") (class "Default")
      (node (ref "C31") (pin "2") (pinfunction "2_2") (pintype "passive"))
      (node (ref "R5") (pin "1") (pinfunction "1_1") (pintype "bidirectional"))
      (node (ref "SW_UP") (pin "2") (pinfunction "2_2") (pintype "passive"))
      (node (ref "U1") (pin "P$AD8") (pinfunction "P0.13_P$AD8") (pintype "bidirectional"))
    )
    (net (code "56") (name "P0.14") (class "Default")
      (node (ref "C30") (pin "2") (pinfunction "2_2") (pintype "passive"))
      (node (ref "R8") (pin "1") (pinfunction "1_1") (pintype "bidirectional"))
      (node (ref "SW_ENT") (pin "2") (pinfunction "2_2") (pintype "passive"))
      (node (ref "U1") (pin "P$AC9") (pinfunction "P0.14_P$AC9") (pintype "bidirectional"))
    )
    (net (code "57") (name "P0.19") (class "Default")
      (node (ref "U1") (pin "P$AC15") (pinfunction "P0.19_P$AC15") (pintype "bidirectional"))
    )
    (net (code "58") (name "P0.20") (class "Default")
      (node (ref "U1") (pin "P$AD16") (pinfunction "P0.20_P$AD16") (pintype "bidirectional"))
    )
    (net (code "59") (name "P0.21") (class "Default")
      (node (ref "U1") (pin "P$AC17") (pinfunction "P0.21_P$AC17") (pintype "bidirectional"))
    )
    (net (code "60") (name "P0.22") (class "Default")
      (node (ref "U1") (pin "P$AD18") (pinfunction "P0.22_P$AD18") (pintype "bidirectional"))
    )
    (net (code "61") (name "P0.23") (class "Default")
      (node (ref "U1") (pin "P$AC19") (pinfunction "P0.23_P$AC19") (pintype "bidirectional"))
    )
    (net (code "62") (name "P0.24") (class "Default")
      (node (ref "U1") (pin "P$AD20") (pinfunction "P0.24_P$AD20") (pintype "bidirectional"))
    )
    (net (code "63") (name "P0.25") (class "Default")
      (node (ref "U1") (pin "P$AC21") (pinfunction "P0.25_P$AC21") (pintype "bidirectional"))
    )
    (net (code "64") (name "P0.26") (class "Default")
      (node (ref "U1") (pin "P$G1") (pinfunction "P0.26_P$G1") (pintype "bidirectional"))
    )
    (net (code "65") (name "P0.27") (class "Default")
      (node (ref "U1") (pin "P$H2") (pinfunction "P0.27_P$H2") (pintype "bidirectional"))
    )
    (net (code "66") (name "P0.28") (class "Default")
      (node (ref "U1") (pin "P$B11") (pinfunction "P0.28/AIN4_P$B11") (pintype "bidirectional"))
    )
    (net (code "67") (name "P0.29") (class "Default")
      (node (ref "U1") (pin "P$A10") (pinfunction "P0.29/AIN5_P$A10") (pintype "bidirectional"))
    )
    (net (code "68") (name "P0.30") (class "Default")
      (node (ref "U1") (pin "P$B9") (pinfunction "P0.30/AIN6_P$B9") (pintype "bidirectional"))
    )
    (net (code "69") (name "P0.31") (class "Default")
      (node (ref "U1") (pin "P$A8") (pinfunction "P0.31/AIN7_P$A8") (pintype "bidirectional"))
    )
    (net (code "70") (name "P1.01") (class "Default")
      (node (ref "Q1") (pin "1") (pinfunction "G_1") (pintype "bidirectional"))
      (node (ref "R_PWR_EPD") (pin "1") (pinfunction "1_1") (pintype "bidirectional"))
      (node (ref "U1") (pin "P$Y23") (pinfunction "P1.01_P$Y23") (pintype "bidirectional"))
    )
    (net (code "71") (name "P1.02") (class "Default")
      (node (ref "C29") (pin "2") (pinfunction "2_2") (pintype "passive"))
      (node (ref "R7") (pin "1") (pinfunction "1_1") (pintype "bidirectional"))
      (node (ref "SW_DN") (pin "2") (pinfunction "2_2") (pintype "passive"))
      (node (ref "U1") (pin "P$W24") (pinfunction "P1.02_P$W24") (pintype "bidirectional"))
    )
    (net (code "72") (name "P1.03") (class "Default")
      (node (ref "U1") (pin "P$V23") (pinfunction "P1.03_P$V23") (pintype "bidirectional"))
    )
    (net (code "73") (name "P1.04") (class "Default")
      (node (ref "U1") (pin "P$U24") (pinfunction "P1.04_P$U24") (pintype "bidirectional"))
    )
    (net (code "74") (name "P1.05") (class "Default")
      (node (ref "U1") (pin "P$T23") (pinfunction "P1.05_P$T23") (pintype "bidirectional"))
    )
    (net (code "75") (name "P1.06") (class "Default")
      (node (ref "U1") (pin "P$R24") (pinfunction "P1.06_P$R24") (pintype "bidirectional"))
    )
    (net (code "76") (name "P1.07") (class "Default")
      (node (ref "U1") (pin "P$P23") (pinfunction "P1.07_P$P23") (pintype "bidirectional"))
    )
    (net (code "77") (name "P1.09") (class "Default")
      (node (ref "U1") (pin "P$R1") (pinfunction "P1.09_P$R1") (pintype "bidirectional"))
    )
    (net (code "78") (name "P1.10") (class "Default")
      (node (ref "U1") (pin "P$A20") (pinfunction "P1.10_P$A20") (pintype "bidirectional"))
    )
    (net (code "79") (name "P1.11") (class "Default")
      (node (ref "U1") (pin "P$B19") (pinfunction "P1.11_P$B19") (pintype "bidirectional"))
    )
    (net (code "80") (name "P1.12") (class "Default")
      (node (ref "U1") (pin "P$B17") (pinfunction "P1.12_P$B17") (pintype "bidirectional"))
    )
    (net (code "81") (name "P1.13") (class "Default")
      (node (ref "U1") (pin "P$A16") (pinfunction "P1.13_P$A16") (pintype "bidirectional"))
    )
    (net (code "82") (name "P1.14") (class "Default")
      (node (ref "U1") (pin "P$B15") (pinfunction "P1.14_P$B15") (pintype "bidirectional"))
    )
    (net (code "83") (name "P1.15") (class "Default")
      (node (ref "U1") (pin "P$A14") (pinfunction "P1.15_P$A14") (pintype "bidirectional"))
    )
    (net (code "84") (name "PMIC_INT") (class "Default")
      (node (ref "IC1") (pin "A1") (pinfunction "~{INT}_A1") (pintype "bidirectional"))
      (node (ref "U1") (pin "P$T2") (pinfunction "P0.11_P$T2") (pintype "bidirectional"))
    )
    (net (code "85") (name "PREVGH") (class "Default")
      (node (ref "D5") (pin "1") (pinfunction "K_1") (pintype "bidirectional"))
      (node (ref "EPD_C9") (pin "2") (pinfunction "2_2") (pintype "passive"))
      (node (ref "J1") (pin "21") (pinfunction "21_21") (pintype "bidirectional"))
    )
    (net (code "86") (name "PREVGL") (class "Default")
      (node (ref "D2") (pin "2") (pinfunction "A_2") (pintype "bidirectional"))
      (node (ref "EPD_C11") (pin "2") (pinfunction "2_2") (pintype "passive"))
      (node (ref "J1") (pin "23") (pinfunction "23_23") (pintype "bidirectional"))
    )
    (net (code "87") (name "RESE") (class "Default")
      (node (ref "J1") (pin "3") (pinfunction "3_3") (pintype "bidirectional"))
      (node (ref "Q3") (pin "2") (pinfunction "S_2") (pintype "bidirectional"))
      (node (ref "R1_EP_DR") (pin "2") (pinfunction "2_2") (pintype "bidirectional"))
    )
    (net (code "88") (name "RESET") (class "Default")
      (node (ref "J2") (pin "6") (pinfunction "6_6") (pintype "bidirectional"))
      (node (ref "TP_RESET") (pin "TP") (pinfunction "TP_TP") (pintype "input"))
      (node (ref "U1") (pin "P$AC13") (pinfunction "P0.18/RESET_P$AC13") (pintype "bidirectional"))
    )
    (net (code "89") (name "SCK") (class "Default")
      (node (ref "J1") (pin "13") (pinfunction "13_13") (pintype "bidirectional"))
      (node (ref "U1") (pin "P$A12") (pinfunction "P0.02/AIN0_P$A12") (pintype "bidirectional"))
    )
    (net (code "90") (name "SCL") (class "Default")
      (node (ref "IC1") (pin "B1") (pinfunction "SCL_B1") (pintype "bidirectional"))
      (node (ref "IC3") (pin "12") (pinfunction "SCX_12") (pintype "bidirectional"))
      (node (ref "IC4") (pin "C1") (pinfunction "SCL_C1") (pintype "bidirectional"))
      (node (ref "R17") (pin "2") (pinfunction "2_2") (pintype "bidirectional"))
      (node (ref "R4") (pin "2") (pinfunction "2_2") (pintype "bidirectional"))
      (node (ref "TP_SCL") (pin "TP") (pinfunction "TP_TP") (pintype "input"))
      (node (ref "U1") (pin "P$M2") (pinfunction "P0.07_P$M2") (pintype "bidirectional"))
      (node (ref "U3") (pin "7") (pinfunction "SCL_7") (pintype "input"))
    )
    (net (code "91") (name "SDA") (class "Default")
      (node (ref "IC1") (pin "C1") (pinfunction "SDA_C1") (pintype "bidirectional"))
      (node (ref "IC3") (pin "2") (pinfunction "SDX_2") (pintype "bidirectional"))
      (node (ref "IC4") (pin "B2") (pinfunction "SDA_B2") (pintype "bidirectional"))
      (node (ref "R18") (pin "2") (pinfunction "2_2") (pintype "bidirectional"))
      (node (ref "R2") (pin "2") (pinfunction "2_2") (pintype "bidirectional"))
      (node (ref "TP_SDA") (pin "TP") (pinfunction "TP_TP") (pintype "input"))
      (node (ref "U1") (pin "P$L1") (pinfunction "P0.06_P$L1") (pintype "bidirectional"))
      (node (ref "U3") (pin "8") (pinfunction "SDA_8") (pintype "bidirectional"))
    )
    (net (code "92") (name "SWDCLK") (class "Default")
      (node (ref "J2") (pin "4") (pinfunction "4_4") (pintype "bidirectional"))
      (node (ref "TP_SWDCLK") (pin "TP") (pinfunction "TP_TP") (pintype "input"))
      (node (ref "U1") (pin "P$AA24") (pinfunction "SWDCLK_P$AA24") (pintype "input"))
    )
    (net (code "93") (name "SWDIO") (class "Default")
      (node (ref "J2") (pin "2") (pinfunction "2_2") (pintype "bidirectional"))
      (node (ref "TP_SWDIO") (pin "TP") (pinfunction "TP_TP") (pintype "input"))
      (node (ref "U1") (pin "P$AC24") (pinfunction "SWDIO_P$AC24") (pintype "bidirectional"))
    )
    (net (code "94") (name "SWO") (class "Default")
      (node (ref "TP_SWO") (pin "TP") (pinfunction "TP_TP") (pintype "input"))
      (node (ref "U1") (pin "P$AD22") (pinfunction "P1.00_P$AD22") (pintype "bidirectional"))
    )
    (net (code "95") (name "VBAT") (class "Default")
      (node (ref "C27") (pin "2") (pinfunction "2_2") (pintype "passive"))
      (node (ref "C37") (pin "2") (pinfunction "2_2") (pintype "passive"))
      (node (ref "IC1") (pin "C2") (pinfunction "BAT_C2") (pintype "bidirectional"))
      (node (ref "TP_VBAT") (pin "TP") (pinfunction "TP_TP") (pintype "input"))
      (node (ref "U3") (pin "2") (pinfunction "CELL_2") (pintype "power_in"))
      (node (ref "U3") (pin "3") (pinfunction "VDD_3") (pintype "power_in"))
    )
    (net (code "96") (name "VBUS") (class "Default")
      (node (ref "C21") (pin "1") (pinfunction "1_1") (pintype "passive"))
      (node (ref "C38") (pin "2") (pinfunction "2_2") (pintype "passive"))
      (node (ref "C42") (pin "1") (pinfunction "1_1") (pintype "passive"))
      (node (ref "C43") (pin "1") (pinfunction "1_1") (pintype "passive"))
      (node (ref "D3") (pin "5") (pinfunction "VBUS_5") (pintype "bidirectional"))
      (node (ref "IC1") (pin "A2") (pinfunction "IN_A2") (pintype "bidirectional"))
      (node (ref "J4") (pin "A4_B9") (pinfunction "VBUS_A4_B9") (pintype "power_in"))
      (node (ref "J4") (pin "A9_B4") (pinfunction "VBUS_A9_B4") (pintype "power_in"))
      (node (ref "U1") (pin "P$AD2") (pinfunction "VBUS_P$AD2") (pintype "power_in"))
    )
    (net (code "97") (name "VREG") (class "Default")
      (node (ref "C23") (pin "1") (pinfunction "1_1") (pintype "passive"))
      (node (ref "C24") (pin "2") (pinfunction "2_2") (pintype "passive"))
      (node (ref "C39") (pin "1") (pinfunction "1_1") (pintype "passive"))
      (node (ref "IC1") (pin "B2") (pinfunction "SYS_B2") (pintype "bidirectional"))
      (node (ref "IC9") (pin "A1") (pinfunction "EN_A1") (pintype "bidirectional"))
      (node (ref "IC9") (pin "A2") (pinfunction "VIN_1_A2") (pintype "bidirectional"))
      (node (ref "IC9") (pin "A3") (pinfunction "VIN_2_A3") (pintype "bidirectional"))
      (node (ref "TP_VREG") (pin "TP") (pinfunction "TP_TP") (pintype "input"))
    )
    (net (code "98") (name "unconnected-(ANT1-NC-Pad2)") (class "Default")
      (node (ref "ANT1") (pin "2") (pinfunction "NC_2") (pintype "no_connect"))
    )
    (net (code "99") (name "unconnected-(IC3-ASCL-Pad11)") (class "Default")
      (node (ref "IC3") (pin "11") (pinfunction "ASCL_11") (pintype "bidirectional"))
    )
    (net (code "100") (name "unconnected-(IC3-ASDA-Pad4)") (class "Default")
      (node (ref "IC3") (pin "4") (pinfunction "ASDA_4") (pintype "bidirectional"))
    )
    (net (code "101") (name "unconnected-(IC9-VOUT_1-PadE2)") (class "Default")
      (node (ref "IC9") (pin "E2") (pinfunction "VOUT_1_E2") (pintype "bidirectional"))
    )
    (net (code "102") (name "unconnected-(J1-Pad1)") (class "Default")
      (node (ref "J1") (pin "1") (pinfunction "1_1") (pintype "bidirectional"))
    )
    (net (code "103") (name "unconnected-(J1-Pad6)") (class "Default")
      (node (ref "J1") (pin "6") (pinfunction "6_6") (pintype "bidirectional"))
    )
    (net (code "104") (name "unconnected-(J1-Pad7)") (class "Default")
      (node (ref "J1") (pin "7") (pinfunction "7_7") (pintype "bidirectional"))
    )
    (net (code "105") (name "unconnected-(J4-SBU1-PadA8)") (class "Default")
      (node (ref "J4") (pin "A8") (pinfunction "SBU1_A8") (pintype "bidirectional"))
    )
    (net (code "106") (name "unconnected-(J4-SBU2-PadB8)") (class "Default")
      (node (ref "J4") (pin "B8") (pinfunction "SBU2_B8") (pintype "bidirectional"))
    )
    (net (code "107") (name "unconnected-(U1-DCCH-PadP$AB2)") (class "Default")
      (node (ref "U1") (pin "P$AB2") (pinfunction "DCCH_P$AB2") (pintype "bidirectional"))
    )
  )
)
